# senror_input.net
KiCad netlist of a schematic drawn in Altium Designer
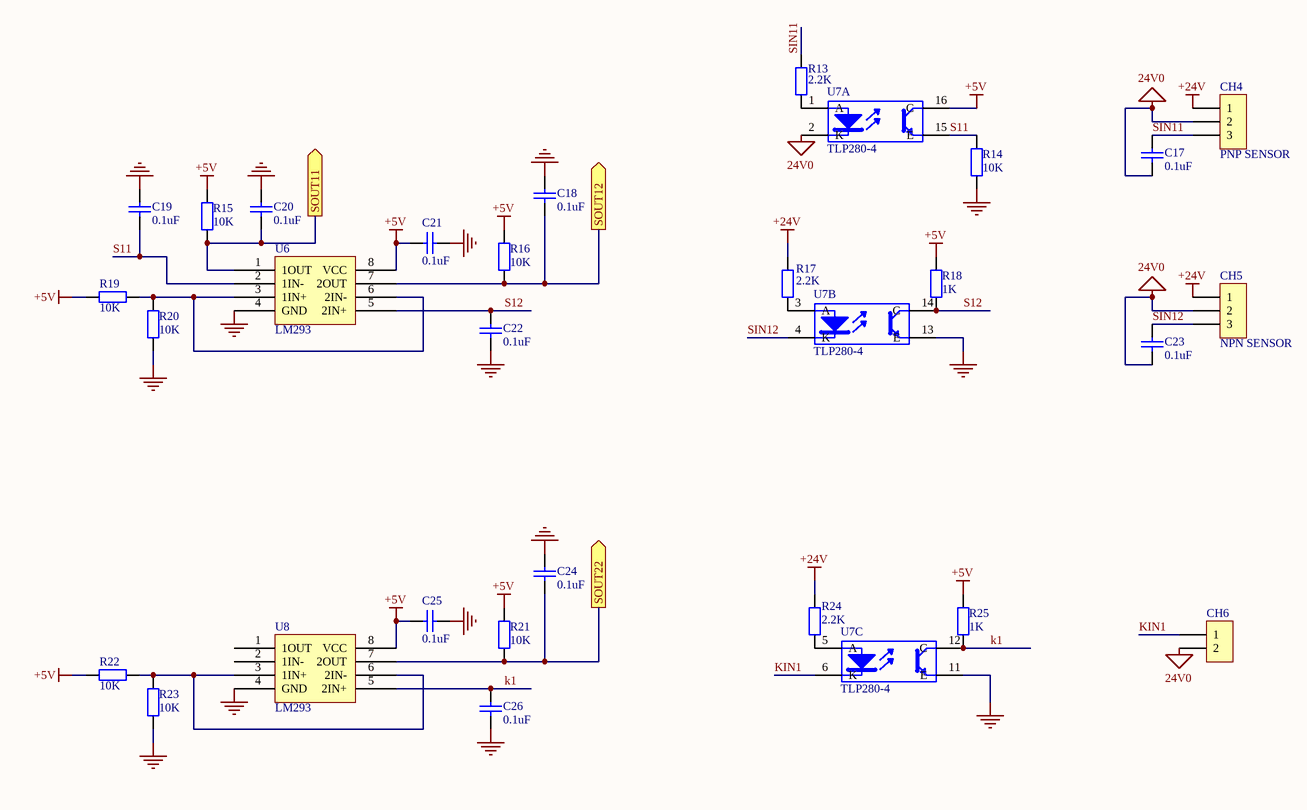
[diagram p0: senror_input.SchDoc]

(export (version "E")
  (design (tool "Eeschema 10.0.6"))
  (components
    (comp (ref "C17")
      (value "0.1uF")
      (footprint "0805")
      (description "Capacitor")
      (fields (field (name "Comment") "Cap") (field (name "PUBLISHER") "Altium Limited"))
      (libsource (lib "Miscellaneous Devices") (part "Cap"))
    )
    (comp (ref "C18")
      (value "0.1uF")
      (footprint "0805")
      (description "Capacitor")
      (fields (field (name "Comment") "Cap") (field (name "PUBLISHER") "Altium Limited"))
      (libsource (lib "Miscellaneous Devices") (part "Cap"))
    )
    (comp (ref "C19")
      (value "0.1uF")
      (footprint "0805")
      (description "Capacitor")
      (fields (field (name "Comment") "Cap") (field (name "PUBLISHER") "Altium Limited"))
      (libsource (lib "Miscellaneous Devices") (part "Cap"))
    )
    (comp (ref "C20")
      (value "0.1uF")
      (footprint "0805")
      (description "Capacitor")
      (fields (field (name "Comment") "Cap") (field (name "PUBLISHER") "Altium Limited"))
      (libsource (lib "Miscellaneous Devices") (part "Cap"))
    )
    (comp (ref "C21")
      (value "0.1uF")
      (footprint "0805")
      (description "Capacitor")
      (fields (field (name "Comment") "Cap") (field (name "PUBLISHER") "Altium Limited"))
      (libsource (lib "Miscellaneous Devices") (part "Cap"))
    )
    (comp (ref "C22")
      (value "0.1uF")
      (footprint "0805")
      (description "Capacitor")
      (fields (field (name "Comment") "Cap") (field (name "PUBLISHER") "Altium Limited"))
      (libsource (lib "Miscellaneous Devices") (part "Cap"))
    )
    (comp (ref "C23")
      (value "0.1uF")
      (footprint "0805")
      (description "Capacitor")
      (fields (field (name "Comment") "Cap") (field (name "PUBLISHER") "Altium Limited"))
      (libsource (lib "Miscellaneous Devices") (part "Cap"))
    )
    (comp (ref "C24")
      (value "0.1uF")
      (footprint "0805")
      (description "Capacitor")
      (fields (field (name "Comment") "Cap") (field (name "PUBLISHER") "Altium Limited"))
      (libsource (lib "Miscellaneous Devices") (part "Cap"))
    )
    (comp (ref "C25")
      (value "0.1uF")
      (footprint "0805")
      (description "Capacitor")
      (fields (field (name "Comment") "Cap") (field (name "PUBLISHER") "Altium Limited"))
      (libsource (lib "Miscellaneous Devices") (part "Cap"))
    )
    (comp (ref "C26")
      (value "0.1uF")
      (footprint "0805")
      (description "Capacitor")
      (fields (field (name "Comment") "Cap") (field (name "PUBLISHER") "Altium Limited"))
      (libsource (lib "Miscellaneous Devices") (part "Cap"))
    )
    (comp (ref "CH4")
      (value "HEADER1X3")
      (footprint "CH3.96-3PIN")
      (fields (field (name "ALTIUM_UNNAMED_1") "PNP SENSOR"))
      (libsource (lib "myIntegrated_Library1") (part "HEADER1X3"))
    )
    (comp (ref "CH5")
      (value "HEADER1X3")
      (footprint "CH3.96-3PIN")
      (fields (field (name "ALTIUM_UNNAMED_1") "NPN SENSOR"))
      (libsource (lib "myIntegrated_Library1") (part "HEADER1X3"))
    )
    (comp (ref "CH6")
      (value "HEADER1X2")
      (footprint "CH3.96-2PIN")
      (libsource (lib "myIntegrated_Library1") (part "HEADER1X2"))
    )
    (comp (ref "R13")
      (value "2.2K")
      (footprint "0805")
      (description "Resistor")
      (fields (field (name "Comment") "Res2") (field (name "PUBLISHER") "Altium Limited"))
      (libsource (lib "Miscellaneous Devices") (part "Res2"))
    )
    (comp (ref "R14")
      (value "10K")
      (footprint "0805")
      (description "Resistor")
      (fields (field (name "Comment") "Res2") (field (name "PUBLISHER") "Altium Limited"))
      (libsource (lib "Miscellaneous Devices") (part "Res2"))
    )
    (comp (ref "R15")
      (value "10K")
      (footprint "0805")
      (description "Resistor")
      (fields (field (name "Comment") "Res2") (field (name "PUBLISHER") "Altium Limited"))
      (libsource (lib "Miscellaneous Devices") (part "Res2"))
    )
    (comp (ref "R16")
      (value "10K")
      (footprint "0805")
      (description "Resistor")
      (fields (field (name "Comment") "Res2") (field (name "PUBLISHER") "Altium Limited"))
      (libsource (lib "Miscellaneous Devices") (part "Res2"))
    )
    (comp (ref "R17")
      (value "2.2K")
      (footprint "0805")
      (description "Resistor")
      (fields (field (name "Comment") "Res2") (field (name "PUBLISHER") "Altium Limited"))
      (libsource (lib "Miscellaneous Devices") (part "Res2"))
    )
    (comp (ref "R18")
      (value "1K")
      (footprint "0805")
      (description "Resistor")
      (fields (field (name "Comment") "Res2") (field (name "PUBLISHER") "Altium Limited"))
      (libsource (lib "Miscellaneous Devices") (part "Res2"))
    )
    (comp (ref "R19")
      (value "10K")
      (footprint "0805")
      (description "Resistor")
      (fields (field (name "Comment") "Res2") (field (name "PUBLISHER") "Altium Limited"))
      (libsource (lib "") (part "Res2_1"))
    )
    (comp (ref "R20")
      (value "10K")
      (footprint "0805")
      (description "Resistor")
      (fields (field (name "Comment") "Res2") (field (name "PUBLISHER") "Altium Limited"))
      (libsource (lib "Miscellaneous Devices") (part "Res2"))
    )
    (comp (ref "R21")
      (value "10K")
      (footprint "0805")
      (description "Resistor")
      (fields (field (name "Comment") "Res2") (field (name "PUBLISHER") "Altium Limited"))
      (libsource (lib "Miscellaneous Devices") (part "Res2"))
    )
    (comp (ref "R22")
      (value "10K")
      (footprint "0805")
      (description "Resistor")
      (fields (field (name "Comment") "Res2") (field (name "PUBLISHER") "Altium Limited"))
      (libsource (lib "") (part "Res2_1"))
    )
    (comp (ref "R23")
      (value "10K")
      (footprint "0805")
      (description "Resistor")
      (fields (field (name "Comment") "Res2") (field (name "PUBLISHER") "Altium Limited"))
      (libsource (lib "Miscellaneous Devices") (part "Res2"))
    )
    (comp (ref "R24")
      (value "2.2K")
      (footprint "0805")
      (description "Resistor")
      (fields (field (name "Comment") "Res2") (field (name "PUBLISHER") "Altium Limited"))
      (libsource (lib "Miscellaneous Devices") (part "Res2"))
    )
    (comp (ref "R25")
      (value "1K")
      (footprint "0805")
      (description "Resistor")
      (fields (field (name "Comment") "Res2") (field (name "PUBLISHER") "Altium Limited"))
      (libsource (lib "Miscellaneous Devices") (part "Res2"))
    )
    (comp (ref "U6")
      (value "LM293")
      (footprint "SOP8-OP27")
      (libsource (lib "myIntegrated_Library1") (part "LM293"))
    )
    (comp (ref "U7") (value "TLP280-4") (footprint "SO16") (libsource (lib "WH V20") (part "TLP521-4")))
    (comp (ref "U8")
      (value "LM293")
      (footprint "SOP8-OP27")
      (libsource (lib "myIntegrated_Library1") (part "LM293"))
    )
  )
  (nets
    (net (code "1") (name "+5V") (class "Default")
      (node (ref "C21") (pin "2") (pinfunction "2_2") (pintype "passive"))
      (node (ref "C25") (pin "2") (pinfunction "2_2") (pintype "passive"))
      (node (ref "R15") (pin "1") (pinfunction "1_1") (pintype "passive"))
      (node (ref "R16") (pin "1") (pinfunction "1_1") (pintype "passive"))
      (node (ref "R18") (pin "1") (pinfunction "1_1") (pintype "passive"))
      (node (ref "R19") (pin "1") (pinfunction "1_1") (pintype "passive"))
      (node (ref "R21") (pin "1") (pinfunction "1_1") (pintype "passive"))
      (node (ref "R22") (pin "1") (pinfunction "1_1") (pintype "passive"))
      (node (ref "R25") (pin "1") (pinfunction "1_1") (pintype "passive"))
      (node (ref "U6") (pin "8") (pinfunction "VCC_8") (pintype "passive"))
      (node (ref "U7") (pin "16") (pinfunction "C_16") (pintype "passive"))
      (node (ref "U8") (pin "8") (pinfunction "VCC_8") (pintype "passive"))
    )
    (net (code "2") (name "+24V") (class "Default")
      (node (ref "CH4") (pin "1") (pinfunction "1_1") (pintype "passive"))
      (node (ref "CH5") (pin "1") (pinfunction "1_1") (pintype "passive"))
      (node (ref "R17") (pin "1") (pinfunction "1_1") (pintype "passive"))
      (node (ref "R24") (pin "1") (pinfunction "1_1") (pintype "passive"))
    )
    (net (code "3") (name "/KIN1") (class "Default")
      (node (ref "CH6") (pin "1") (pinfunction "1_1") (pintype "passive"))
      (node (ref "U7") (pin "6") (pinfunction "K_6") (pintype "passive"))
    )
    (net (code "4") (name "/S11") (class "Default")
      (node (ref "C19") (pin "2") (pinfunction "2_2") (pintype "passive"))
      (node (ref "R14") (pin "1") (pinfunction "1_1") (pintype "passive"))
      (node (ref "U6") (pin "2") (pinfunction "1IN-_2") (pintype "passive"))
      (node (ref "U7") (pin "15") (pinfunction "E_15") (pintype "passive"))
    )
    (net (code "5") (name "/S12") (class "Default")
      (node (ref "C22") (pin "2") (pinfunction "2_2") (pintype "passive"))
      (node (ref "R18") (pin "2") (pinfunction "2_2") (pintype "passive"))
      (node (ref "U6") (pin "5") (pinfunction "2IN+_5") (pintype "passive"))
      (node (ref "U7") (pin "14") (pinfunction "C_14") (pintype "passive"))
    )
    (net (code "6") (name "/SIN11") (class "Default")
      (node (ref "C17") (pin "1") (pinfunction "1_1") (pintype "passive"))
      (node (ref "CH4") (pin "3") (pinfunction "3_3") (pintype "passive"))
      (node (ref "R13") (pin "1") (pinfunction "1_1") (pintype "passive"))
    )
    (net (code "7") (name "/SIN12") (class "Default")
      (node (ref "C23") (pin "1") (pinfunction "1_1") (pintype "passive"))
      (node (ref "CH5") (pin "3") (pinfunction "3_3") (pintype "passive"))
      (node (ref "U7") (pin "4") (pinfunction "K_4") (pintype "passive"))
    )
    (net (code "8") (name "/SOUT11") (class "Default")
      (node (ref "C20") (pin "2") (pinfunction "2_2") (pintype "passive"))
      (node (ref "R15") (pin "2") (pinfunction "2_2") (pintype "passive"))
      (node (ref "U6") (pin "1") (pinfunction "1OUT_1") (pintype "passive"))
    )
    (net (code "9") (name "/SOUT12") (class "Default")
      (node (ref "C18") (pin "2") (pinfunction "2_2") (pintype "passive"))
      (node (ref "R16") (pin "2") (pinfunction "2_2") (pintype "passive"))
      (node (ref "U6") (pin "7") (pinfunction "2OUT_7") (pintype "passive"))
    )
    (net (code "10") (name "/SOUT22") (class "Default")
      (node (ref "C24") (pin "2") (pinfunction "2_2") (pintype "passive"))
      (node (ref "R21") (pin "2") (pinfunction "2_2") (pintype "passive"))
      (node (ref "U8") (pin "7") (pinfunction "2OUT_7") (pintype "passive"))
    )
    (net (code "11") (name "/k1") (class "Default")
      (node (ref "C26") (pin "2") (pinfunction "2_2") (pintype "passive"))
      (node (ref "R25") (pin "2") (pinfunction "2_2") (pintype "passive"))
      (node (ref "U7") (pin "12") (pinfunction "C_12") (pintype "passive"))
      (node (ref "U8") (pin "5") (pinfunction "2IN+_5") (pintype "passive"))
    )
    (net (code "12") (name "24V0") (class "Default")
      (node (ref "C17") (pin "2") (pinfunction "2_2") (pintype "passive"))
      (node (ref "C23") (pin "2") (pinfunction "2_2") (pintype "passive"))
      (node (ref "CH4") (pin "2") (pinfunction "2_2") (pintype "passive"))
      (node (ref "CH5") (pin "2") (pinfunction "2_2") (pintype "passive"))
      (node (ref "CH6") (pin "2") (pinfunction "2_2") (pintype "passive"))
      (node (ref "U7") (pin "2") (pinfunction "K_2") (pintype "passive"))
    )
    (net (code "13") (name "GND") (class "Default")
      (node (ref "C18") (pin "1") (pinfunction "1_1") (pintype "passive"))
      (node (ref "C19") (pin "1") (pinfunction "1_1") (pintype "passive"))
      (node (ref "C20") (pin "1") (pinfunction "1_1") (pintype "passive"))
      (node (ref "C21") (pin "1") (pinfunction "1_1") (pintype "passive"))
      (node (ref "C22") (pin "1") (pinfunction "1_1") (pintype "passive"))
      (node (ref "C24") (pin "1") (pinfunction "1_1") (pintype "passive"))
      (node (ref "C25") (pin "1") (pinfunction "1_1") (pintype "passive"))
      (node (ref "C26") (pin "1") (pinfunction "1_1") (pintype "passive"))
      (node (ref "R14") (pin "2") (pinfunction "2_2") (pintype "passive"))
      (node (ref "R20") (pin "2") (pinfunction "2_2") (pintype "passive"))
      (node (ref "R23") (pin "2") (pinfunction "2_2") (pintype "passive"))
      (node (ref "U6") (pin "4") (pinfunction "GND_4") (pintype "passive"))
      (node (ref "U7") (pin "11") (pinfunction "E_11") (pintype "passive"))
      (node (ref "U7") (pin "13") (pinfunction "E_13") (pintype "passive"))
      (node (ref "U8") (pin "4") (pinfunction "GND_4") (pintype "passive"))
    )
    (net (code "14") (name "Net-(U6-1IN+)") (class "Default")
      (node (ref "R19") (pin "2") (pinfunction "2_2") (pintype "passive"))
      (node (ref "R20") (pin "1") (pinfunction "1_1") (pintype "passive"))
      (node (ref "U6") (pin "3") (pinfunction "1IN+_3") (pintype "passive"))
      (node (ref "U6") (pin "6") (pinfunction "2IN-_6") (pintype "passive"))
    )
    (net (code "15") (name "Net-(U7A-A)") (class "Default")
      (node (ref "R13") (pin "2") (pinfunction "2_2") (pintype "passive"))
      (node (ref "U7") (pin "1") (pinfunction "A_1") (pintype "passive"))
    )
    (net (code "16") (name "Net-(U7B-A)") (class "Default")
      (node (ref "R17") (pin "2") (pinfunction "2_2") (pintype "passive"))
      (node (ref "U7") (pin "3") (pinfunction "A_3") (pintype "passive"))
    )
    (net (code "17") (name "Net-(U7C-A)") (class "Default")
      (node (ref "R24") (pin "2") (pinfunction "2_2") (pintype "passive"))
      (node (ref "U7") (pin "5") (pinfunction "A_5") (pintype "passive"))
    )
    (net (code "18") (name "Net-(U8-1IN+)") (class "Default")
      (node (ref "R22") (pin "2") (pinfunction "2_2") (pintype "passive"))
      (node (ref "R23") (pin "1") (pinfunction "1_1") (pintype "passive"))
      (node (ref "U8") (pin "3") (pinfunction "1IN+_3") (pintype "passive"))
      (node (ref "U8") (pin "6") (pinfunction "2IN-_6") (pintype "passive"))
    )
    (net (code "19") (name "unconnected-(U8-1IN--Pad2)") (class "Default")
      (node (ref "U8") (pin "2") (pinfunction "1IN-_2") (pintype "passive"))
    )
    (net (code "20") (name "unconnected-(U8-1OUT-Pad1)") (class "Default")
      (node (ref "U8") (pin "1") (pinfunction "1OUT_1") (pintype "passive"))
    )
  )
)
